# IDD_measurement.net
KiCad netlist of a schematic drawn in Altium Designer
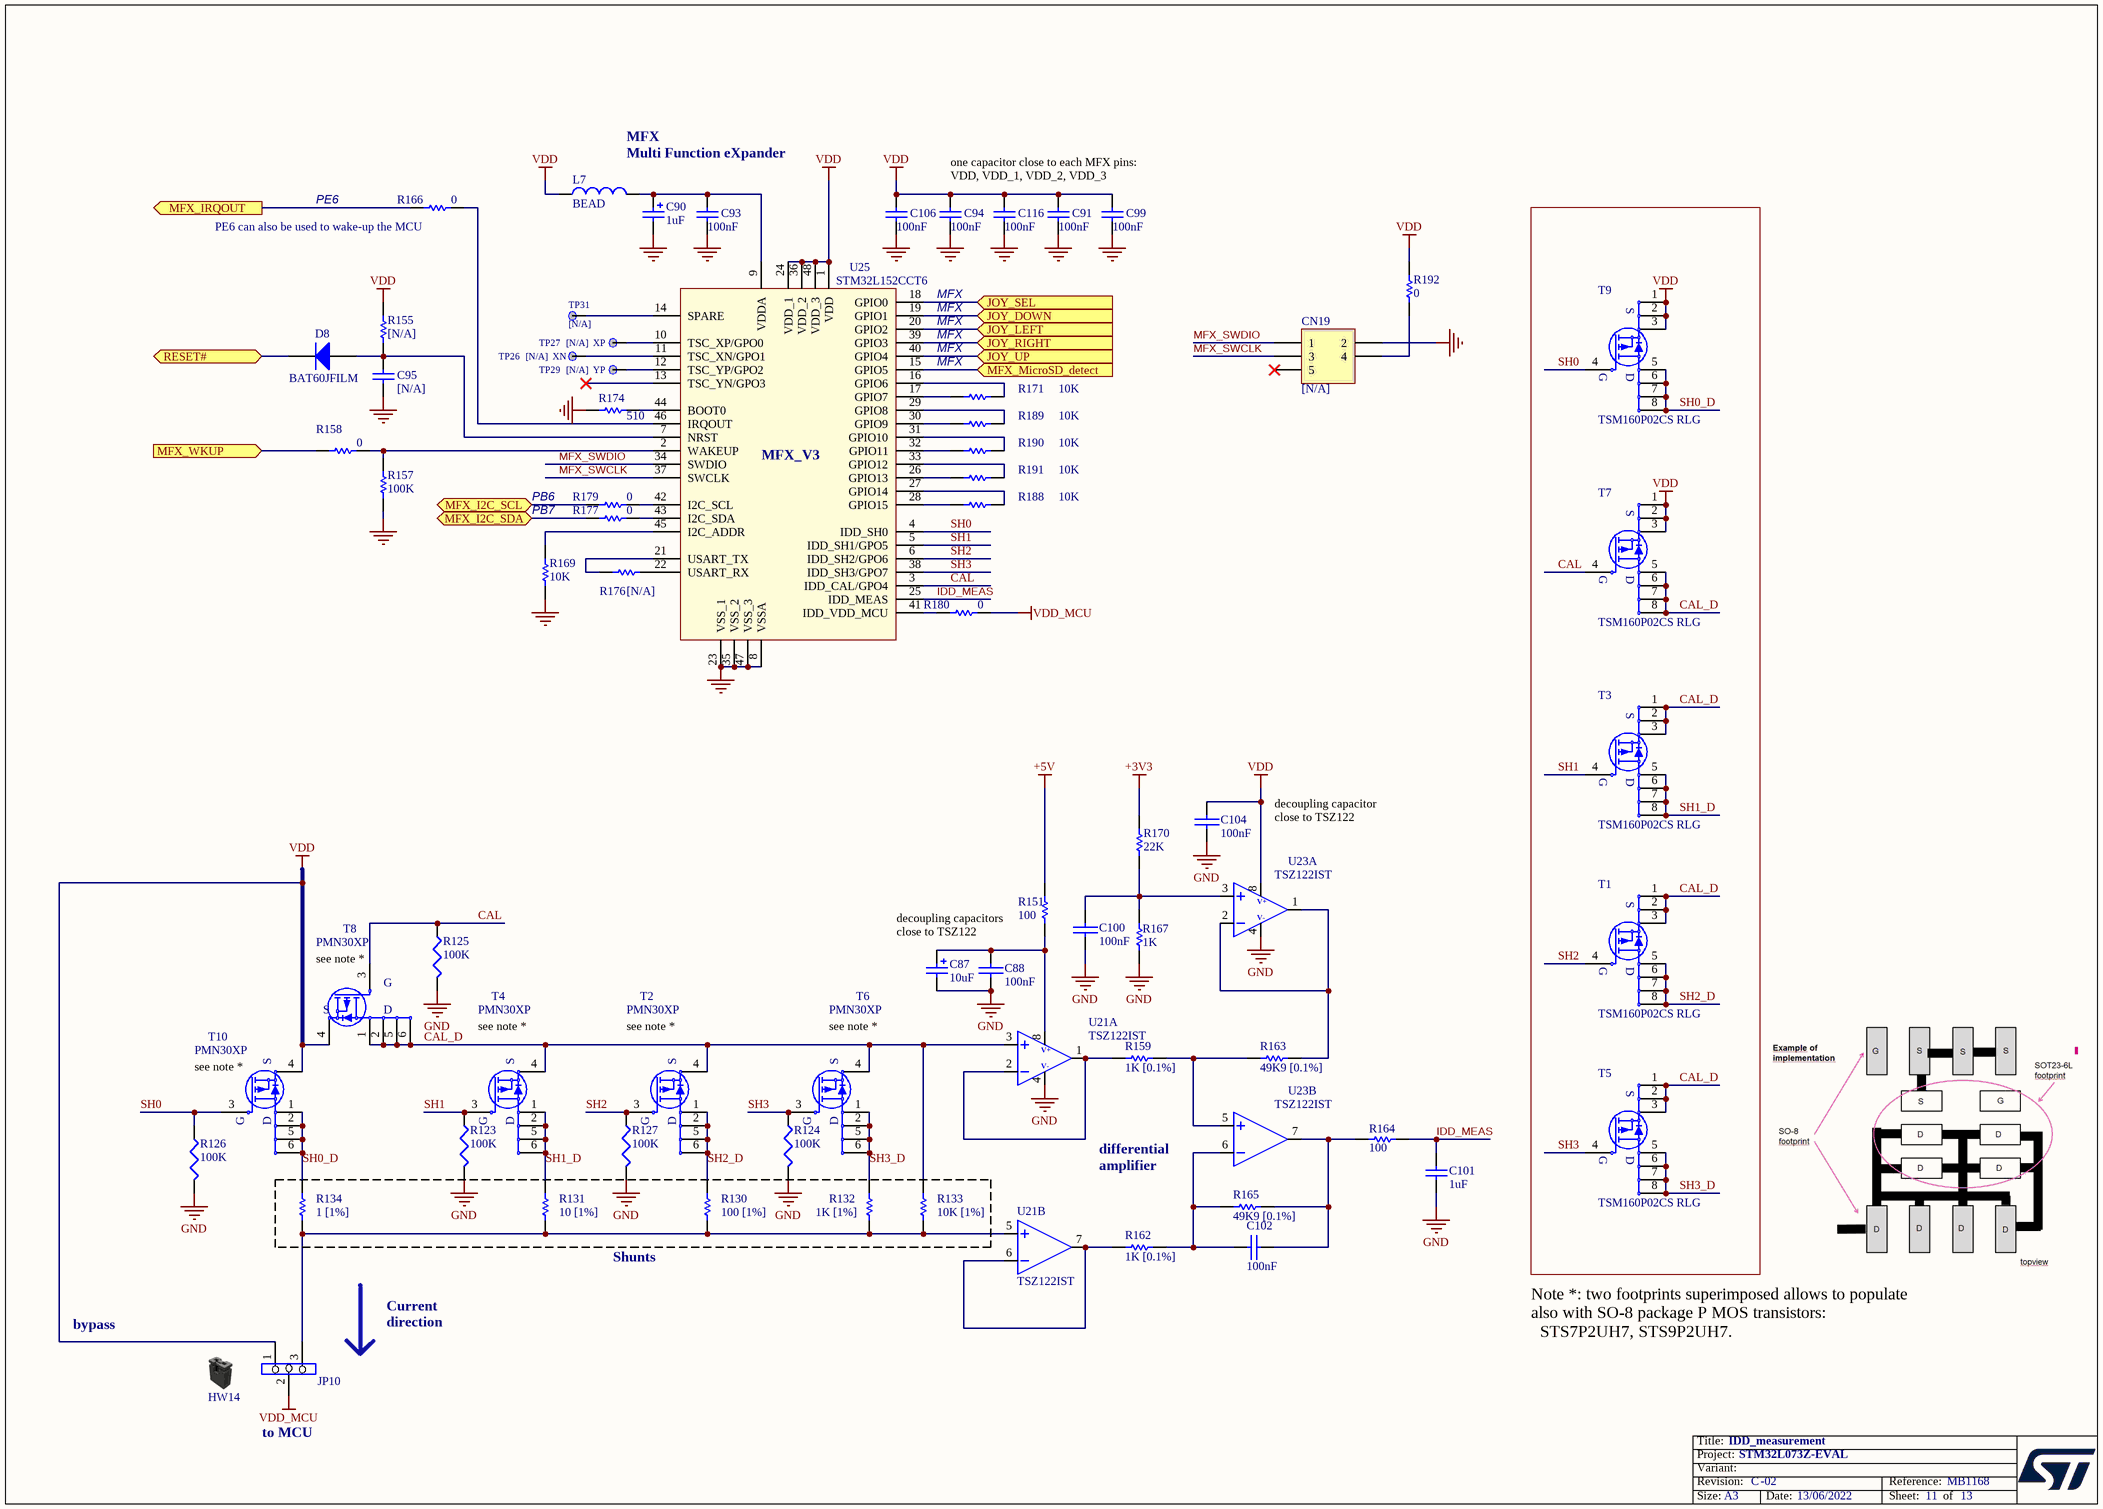
[diagram p0: IDD_measurement.SchDoc]

(export (version "E")
  (design (tool "Eeschema 10.0.6"))
  (components
    (comp (ref "C87")
      (value "10uF")
      (footprint "TAN-A")
      (description "Polarized Capacitor (Radial)")
      (fields (field (name "PUBLISHER") "Altium Limited"))
      (libsource (lib "Miscellaneous Devices") (part "Cap Pol1"))
    )
    (comp (ref "C88") (value "100nF") (footprint "0402C") (libsource (lib "*") (part "CAP")))
    (comp (ref "C90")
      (value "1uF")
      (footprint "TAN-A")
      (description "Polarized Capacitor")
      (libsource (lib "MCD_TOOLS") (part "Cap_1uF_POL_10%_TANA"))
    )
    (comp (ref "C91")
      (value "100nF")
      (footprint "0402C")
      (description "Capacitor,100nF,16V,X7R,10%,0402,YAGEO")
      (libsource (lib "MCD_TOOLS") (part "Cap_100nF_X7R_10%_0402"))
    )
    (comp (ref "C93")
      (value "100nF")
      (footprint "0402C")
      (description "Capacitor,100nF,16V,X7R,10%,0402,YAGEO")
      (libsource (lib "MCD_TOOLS") (part "Cap_100nF_X7R_10%_0402"))
    )
    (comp (ref "C94")
      (value "100nF")
      (footprint "0402C")
      (description "Capacitor,100nF,16V,X7R,10%,0402,YAGEO")
      (libsource (lib "MCD_TOOLS") (part "Cap_100nF_X7R_10%_0402"))
    )
    (comp (ref "C95")
      (value "[N/A]")
      (footprint "0603C")
      (description "Capacitor")
      (fields (field (name "PUBLISHER") "Altium Limited"))
      (libsource (lib "Miscellaneous Devices") (part "cap"))
    )
    (comp (ref "C99")
      (value "100nF")
      (footprint "0402C")
      (description "Capacitor,100nF,16V,X7R,10%,0402,YAGEO")
      (libsource (lib "MCD_TOOLS") (part "Cap_100nF_X7R_10%_0402"))
    )
    (comp (ref "C100") (value "100nF") (footprint "0402C") (libsource (lib "*") (part "CAP")))
    (comp (ref "C101")
      (value "1uF")
      (footprint "0603C")
      (description "Capacitor")
      (fields (field (name "PUBLISHER") "Altium Limited"))
      (libsource (lib "Miscellaneous Devices") (part "CAP"))
    )
    (comp (ref "C102") (value "100nF") (footprint "0402C") (libsource (lib "*") (part "CAP")))
    (comp (ref "C104") (value "100nF") (footprint "0402C") (libsource (lib "*") (part "CAP")))
    (comp (ref "C106")
      (value "100nF")
      (footprint "0402C")
      (description "Capacitor,100nF,16V,X7R,10%,0402,YAGEO")
      (libsource (lib "MCD_TOOLS") (part "Cap_100nF_X7R_10%_0402"))
    )
    (comp (ref "C116")
      (value "100nF")
      (footprint "0402C")
      (description "Capacitor,100nF,16V,X7R,10%,0402,YAGEO")
      (libsource (lib "MCD_TOOLS") (part "Cap_100nF_X7R_10%_0402"))
    )
    (comp (ref "CN19")
      (value "[N/A]")
      (footprint "HDR_2X3-1_2R54-6")
      (description "Header, 3-Pin, Dual row")
      (fields (field (name "PUBLISHER") "Altium Limited"))
      (libsource (lib "Miscellaneous Connectors") (part "Header 3X2"))
    )
    (comp (ref "D8")
      (value "BAT60JFILM")
      (footprint "SOD-323")
      (description "Default Diode")
      (fields (field (name "PUBLISHER") "Altium Limited"))
      (libsource (lib "MB1144_1") (part "Diode"))
    )
    (comp (ref "HW14") (value "Shunt Black 2.54mm") (libsource (lib "MB1168") (part "Shunt Black 2.54mm")))
    (comp (ref "JP10") (value "~") (footprint "SIP3") (libsource (lib "STR910_SCHLIB") (part "Jumper3")))
    (comp (ref "L7")
      (value "BEAD")
      (footprint "0603L")
      (description "Bead,600R,350mA,0603")
      (libsource (lib "MCD_TOOLS") (part "BEAD_600R_350MA_0603"))
    )
    (comp (ref "R123")
      (value "100K")
      (footprint "0402R")
      (description "Resistor")
      (libsource (lib "*") (part "RES1"))
    )
    (comp (ref "R124")
      (value "100K")
      (footprint "0402R")
      (description "Resistor")
      (libsource (lib "*") (part "RES1"))
    )
    (comp (ref "R125")
      (value "100K")
      (footprint "0402R")
      (description "Resistor")
      (libsource (lib "*") (part "RES1"))
    )
    (comp (ref "R126")
      (value "100K")
      (footprint "0402R")
      (description "Resistor")
      (libsource (lib "*") (part "RES1"))
    )
    (comp (ref "R127")
      (value "100K")
      (footprint "0402R")
      (description "Resistor")
      (libsource (lib "*") (part "RES1"))
    )
    (comp (ref "R130")
      (value "100 [1%]")
      (footprint "0603R")
      (description "Resistor")
      (fields (field (name "PUBLISHER") "Altium Limited"))
      (libsource (lib "Miscellaneous Devices") (part "res1"))
    )
    (comp (ref "R131")
      (value "10 [1%]")
      (footprint "0603R")
      (description "Resistor")
      (fields (field (name "PUBLISHER") "Altium Limited"))
      (libsource (lib "Miscellaneous Devices") (part "res1"))
    )
    (comp (ref "R132")
      (value "1K [1%]")
      (footprint "0603R")
      (description "Resistor")
      (fields (field (name "PUBLISHER") "Altium Limited"))
      (libsource (lib "Miscellaneous Devices") (part "res1"))
    )
    (comp (ref "R133")
      (value "10K [1%]")
      (footprint "0603R")
      (description "Resistor")
      (fields (field (name "PUBLISHER") "Altium Limited"))
      (libsource (lib "Miscellaneous Devices") (part "res1"))
    )
    (comp (ref "R134")
      (value "1 [1%]")
      (footprint "0603R")
      (description "Resistor")
      (fields (field (name "PUBLISHER") "Altium Limited"))
      (libsource (lib "Miscellaneous Devices") (part "res1"))
    )
    (comp (ref "R151")
      (value "100")
      (footprint "0402R")
      (description "Resistor")
      (fields (field (name "PUBLISHER") "Altium Limited"))
      (libsource (lib "Miscellaneous Devices") (part "res1"))
    )
    (comp (ref "R155")
      (value "[N/A]")
      (footprint "0603R")
      (description "Resistor")
      (fields (field (name "PUBLISHER") "Altium Limited"))
      (libsource (lib "Miscellaneous Devices") (part "Res1"))
    )
    (comp (ref "R157")
      (value "100K")
      (footprint "0402R")
      (description "Resistor 0402 / 0603 / 0805")
      (libsource (lib "MCD_TOOLS") (part "Resistor_ST"))
    )
    (comp (ref "R158")
      (value "0")
      (footprint "0603R")
      (description "Resistor")
      (fields (field (name "PUBLISHER") "Altium Limited"))
      (libsource (lib "Miscellaneous Devices") (part "Res1"))
    )
    (comp (ref "R159")
      (value "1K [0.1%]")
      (footprint "0603R")
      (description "Resistor")
      (fields (field (name "PUBLISHER") "Altium Limited"))
      (libsource (lib "Miscellaneous Devices") (part "res1"))
    )
    (comp (ref "R162")
      (value "1K [0.1%]")
      (footprint "0603R")
      (description "Resistor")
      (fields (field (name "PUBLISHER") "Altium Limited"))
      (libsource (lib "Miscellaneous Devices") (part "res1"))
    )
    (comp (ref "R163")
      (value "49K9 [0.1%]")
      (footprint "0603R")
      (description "Resistor")
      (fields (field (name "PUBLISHER") "Altium Limited"))
      (libsource (lib "Miscellaneous Devices") (part "res1"))
    )
    (comp (ref "R164")
      (value "100")
      (footprint "0402R")
      (description "Resistor")
      (fields (field (name "PUBLISHER") "Altium Limited"))
      (libsource (lib "Miscellaneous Devices") (part "Res1"))
    )
    (comp (ref "R165")
      (value "49K9 [0.1%]")
      (footprint "0603R")
      (description "Resistor")
      (fields (field (name "PUBLISHER") "Altium Limited"))
      (libsource (lib "Miscellaneous Devices") (part "res1"))
    )
    (comp (ref "R166")
      (value "0")
      (footprint "0603R")
      (description "Resistor")
      (fields (field (name "PUBLISHER") "Altium Limited"))
      (libsource (lib "Miscellaneous Devices") (part "Res1"))
    )
    (comp (ref "R167")
      (value "1K")
      (footprint "0402R")
      (description "Resistor")
      (fields (field (name "PUBLISHER") "Altium Limited"))
      (libsource (lib "Miscellaneous Devices") (part "Res1"))
    )
    (comp (ref "R169")
      (value "10K")
      (footprint "0603R")
      (description "Resistor")
      (fields (field (name "PUBLISHER") "Altium Limited"))
      (libsource (lib "Miscellaneous Devices") (part "res1"))
    )
    (comp (ref "R170")
      (value "22K")
      (footprint "0603R")
      (description "Resistor")
      (fields (field (name "PUBLISHER") "Altium Limited"))
      (libsource (lib "Miscellaneous Devices") (part "res1"))
    )
    (comp (ref "R171")
      (value "10K")
      (footprint "0603R")
      (description "Resistor")
      (fields (field (name "PUBLISHER") "Altium Limited"))
      (libsource (lib "Miscellaneous Devices") (part "res1"))
    )
    (comp (ref "R174")
      (value "510")
      (footprint "0402R")
      (description "Resistor 0402 / 0603 / 0805")
      (libsource (lib "MCD_TOOLS") (part "Resistor_ST"))
    )
    (comp (ref "R176")
      (value "[N/A]")
      (footprint "0603R")
      (description "Resistor")
      (fields (field (name "PUBLISHER") "Altium Limited"))
      (libsource (lib "Miscellaneous Devices") (part "res1"))
    )
    (comp (ref "R177")
      (value "0")
      (footprint "0603R")
      (description "Resistor")
      (fields (field (name "PUBLISHER") "Altium Limited"))
      (libsource (lib "Miscellaneous Devices") (part "Res1"))
    )
    (comp (ref "R179")
      (value "0")
      (footprint "0603R")
      (description "Resistor")
      (fields (field (name "PUBLISHER") "Altium Limited"))
      (libsource (lib "Miscellaneous Devices") (part "Res1"))
    )
    (comp (ref "R180")
      (value "0")
      (footprint "0603R")
      (description "Resistor")
      (fields (field (name "PUBLISHER") "Altium Limited"))
      (libsource (lib "Miscellaneous Devices") (part "Res1"))
    )
    (comp (ref "R188")
      (value "10K")
      (footprint "0603R")
      (description "Resistor")
      (fields (field (name "PUBLISHER") "Altium Limited"))
      (libsource (lib "Miscellaneous Devices") (part "res1"))
    )
    (comp (ref "R189")
      (value "10K")
      (footprint "0603R")
      (description "Resistor")
      (fields (field (name "PUBLISHER") "Altium Limited"))
      (libsource (lib "Miscellaneous Devices") (part "res1"))
    )
    (comp (ref "R190")
      (value "10K")
      (footprint "0603R")
      (description "Resistor")
      (fields (field (name "PUBLISHER") "Altium Limited"))
      (libsource (lib "Miscellaneous Devices") (part "res1"))
    )
    (comp (ref "R191")
      (value "10K")
      (footprint "0603R")
      (description "Resistor")
      (fields (field (name "PUBLISHER") "Altium Limited"))
      (libsource (lib "Miscellaneous Devices") (part "res1"))
    )
    (comp (ref "R192")
      (value "0")
      (footprint "0603R")
      (description "Resistor")
      (fields (field (name "PUBLISHER") "Altium Limited"))
      (libsource (lib "Miscellaneous Devices") (part "Res1"))
    )
    (comp (ref "T1")
      (value "TSM160P02CS RLG")
      (footprint "SOIC8_1R27_4R9X6")
      (description "STripFET VII Power MOSFET, P-CHANNEL 20V - 0.023 - 7A - SO-8")
      (libsource (lib "MCD_TOOLS") (part "STS7P2UH7"))
    )
    (comp (ref "T2")
      (value "PMN30XP")
      (footprint "SOT23-6L")
      (description "STripFET VII DeepGATE Power MOSFET, P-CHANNEL 20 V, 0.0146, 7 A - SOT23-6L")
      (libsource (lib "MCD_TOOLS") (part "STT7P2UH7"))
    )
    (comp (ref "T3")
      (value "TSM160P02CS RLG")
      (footprint "SOIC8_1R27_4R9X6")
      (description "STripFET VII Power MOSFET, P-CHANNEL 20V - 0.023 - 7A - SO-8")
      (libsource (lib "MCD_TOOLS") (part "STS7P2UH7"))
    )
    (comp (ref "T4")
      (value "PMN30XP")
      (footprint "SOT23-6L")
      (description "STripFET VII DeepGATE Power MOSFET, P-CHANNEL 20 V, 0.0146, 7 A - SOT23-6L")
      (libsource (lib "MCD_TOOLS") (part "STT7P2UH7"))
    )
    (comp (ref "T5")
      (value "TSM160P02CS RLG")
      (footprint "SOIC8_1R27_4R9X6")
      (description "STripFET VII Power MOSFET, P-CHANNEL 20V - 0.023 - 7A - SO-8")
      (libsource (lib "MCD_TOOLS") (part "STS7P2UH7"))
    )
    (comp (ref "T6")
      (value "PMN30XP")
      (footprint "SOT23-6L")
      (description "STripFET VII DeepGATE Power MOSFET, P-CHANNEL 20 V, 0.0146, 7 A - SOT23-6L")
      (libsource (lib "MCD_TOOLS") (part "STT7P2UH7"))
    )
    (comp (ref "T7")
      (value "TSM160P02CS RLG")
      (footprint "SOIC8_1R27_4R9X6")
      (description "STripFET VII Power MOSFET, P-CHANNEL 20V - 0.023 - 7A - SO-8")
      (libsource (lib "MCD_TOOLS") (part "STS7P2UH7"))
    )
    (comp (ref "T8")
      (value "PMN30XP")
      (footprint "SOT23-6L")
      (description "STripFET VII DeepGATE Power MOSFET, P-CHANNEL 20 V, 0.0146, 7 A - SOT23-6L")
      (libsource (lib "MCD_TOOLS") (part "STT7P2UH7"))
    )
    (comp (ref "T9")
      (value "TSM160P02CS RLG")
      (footprint "SOIC8_1R27_4R9X6")
      (description "STripFET VII Power MOSFET, P-CHANNEL 20V - 0.023 - 7A - SO-8")
      (libsource (lib "MCD_TOOLS") (part "STS7P2UH7"))
    )
    (comp (ref "T10")
      (value "PMN30XP")
      (footprint "SOT23-6L")
      (description "STripFET VII DeepGATE Power MOSFET, P-CHANNEL 20 V, 0.0146, 7 A - SOT23-6L")
      (libsource (lib "MCD_TOOLS") (part "STT7P2UH7"))
    )
    (comp (ref "TP26")
      (value "[N/A]")
      (footprint "TP")
      (fields (field (name "SILKSCREEN") "XN"))
      (libsource (lib "*") (part "TP"))
    )
    (comp (ref "TP27")
      (value "[N/A]")
      (footprint "TP")
      (fields (field (name "SILKSCREEN") "XP"))
      (libsource (lib "*") (part "TP"))
    )
    (comp (ref "TP29")
      (value "[N/A]")
      (footprint "TP")
      (fields (field (name "SILKSCREEN") "YP"))
      (libsource (lib "*") (part "TP"))
    )
    (comp (ref "TP31") (value "[N/A]") (footprint "TP") (libsource (lib "*") (part "TP")))
    (comp (ref "U21")
      (value "TSZ122IST")
      (footprint "MSOP8_0R65_3X4R9")
      (libsource (lib "Lib_stella") (part "AOP-8PINS"))
    )
    (comp (ref "U23")
      (value "TSZ122IST")
      (footprint "MSOP8_0R65_3X4R9")
      (libsource (lib "Lib_stella") (part "AOP-8PINS"))
    )
    (comp (ref "U25")
      (value "STM32L152CCT6")
      (footprint "LQFP48_0R5_9X9")
      (description "Multifunction expander")
      (libsource (lib "MB1168_1") (part "MFX_V3"))
    )
  )
  (nets
    (net (code "1") (name "+3V3") (class "Default")
      (node (ref "R170") (pin "1") (pinfunction "1_1") (pintype "passive"))
    )
    (net (code "2") (name "+5V") (class "Default")
      (node (ref "R151") (pin "1") (pinfunction "1_1") (pintype "passive"))
    )
    (net (code "3") (name "/CAL") (class "Default")
      (node (ref "R125") (pin "1") (pinfunction "1_1") (pintype "passive"))
      (node (ref "T7") (pin "4") (pinfunction "G_4") (pintype "passive"))
      (node (ref "T8") (pin "3") (pinfunction "G_3") (pintype "passive"))
      (node (ref "U25") (pin "3") (pinfunction "IDD_CAL/GPO4_3") (pintype "passive"))
    )
    (net (code "4") (name "/CAL_D") (class "Default")
      (node (ref "R133") (pin "2") (pinfunction "2_2") (pintype "passive"))
      (node (ref "T1") (pin "1") (pinfunction "S_1") (pintype "passive"))
      (node (ref "T1") (pin "2") (pinfunction "S_2") (pintype "passive"))
      (node (ref "T1") (pin "3") (pinfunction "S_3") (pintype "passive"))
      (node (ref "T2") (pin "4") (pinfunction "S_4") (pintype "passive"))
      (node (ref "T3") (pin "1") (pinfunction "S_1") (pintype "passive"))
      (node (ref "T3") (pin "2") (pinfunction "S_2") (pintype "passive"))
      (node (ref "T3") (pin "3") (pinfunction "S_3") (pintype "passive"))
      (node (ref "T4") (pin "4") (pinfunction "S_4") (pintype "passive"))
      (node (ref "T5") (pin "1") (pinfunction "S_1") (pintype "passive"))
      (node (ref "T5") (pin "2") (pinfunction "S_2") (pintype "passive"))
      (node (ref "T5") (pin "3") (pinfunction "S_3") (pintype "passive"))
      (node (ref "T6") (pin "4") (pinfunction "S_4") (pintype "passive"))
      (node (ref "T7") (pin "5") (pinfunction "D_5") (pintype "passive"))
      (node (ref "T7") (pin "6") (pinfunction "D_6") (pintype "passive"))
      (node (ref "T7") (pin "7") (pinfunction "D_7") (pintype "passive"))
      (node (ref "T7") (pin "8") (pinfunction "D_8") (pintype "passive"))
      (node (ref "T8") (pin "1") (pinfunction "S_1") (pintype "passive"))
      (node (ref "T8") (pin "2") (pinfunction "S_2") (pintype "passive"))
      (node (ref "T8") (pin "5") (pinfunction "D_5") (pintype "passive"))
      (node (ref "T8") (pin "6") (pinfunction "D_6") (pintype "passive"))
      (node (ref "U21") (pin "3") (pintype "passive"))
    )
    (net (code "5") (name "/IDD_MEAS") (class "Default")
      (node (ref "C101") (pin "2") (pinfunction "2_2") (pintype "passive"))
      (node (ref "R164") (pin "1") (pinfunction "1_1") (pintype "passive"))
      (node (ref "U25") (pin "25") (pinfunction "IDD_MEAS_25") (pintype "passive"))
    )
    (net (code "6") (name "/JOY_DOWN") (class "Default")
      (node (ref "U25") (pin "19") (pinfunction "GPIO1_19") (pintype "passive"))
    )
    (net (code "7") (name "/JOY_LEFT") (class "Default")
      (node (ref "U25") (pin "20") (pinfunction "GPIO2_20") (pintype "passive"))
    )
    (net (code "8") (name "/JOY_RIGHT") (class "Default")
      (node (ref "U25") (pin "39") (pinfunction "GPIO3_39") (pintype "passive"))
    )
    (net (code "9") (name "/JOY_SEL") (class "Default")
      (node (ref "U25") (pin "18") (pinfunction "GPIO0_18") (pintype "passive"))
    )
    (net (code "10") (name "/JOY_UP") (class "Default")
      (node (ref "U25") (pin "40") (pinfunction "GPIO4_40") (pintype "passive"))
    )
    (net (code "11") (name "/MFX_I2C_SCL") (class "Default")
      (node (ref "R179") (pin "1") (pinfunction "1_1") (pintype "passive"))
    )
    (net (code "12") (name "/MFX_I2C_SDA") (class "Default")
      (node (ref "R177") (pin "1") (pinfunction "1_1") (pintype "passive"))
    )
    (net (code "13") (name "/MFX_IRQOUT") (class "Default")
      (node (ref "R166") (pin "1") (pinfunction "1_1") (pintype "passive"))
    )
    (net (code "14") (name "/MFX_MicroSD_detect") (class "Default")
      (node (ref "U25") (pin "15") (pinfunction "GPIO5_15") (pintype "passive"))
    )
    (net (code "15") (name "/MFX_SWCLK") (class "Default")
      (node (ref "CN19") (pin "3") (pinfunction "3_3") (pintype "passive"))
      (node (ref "U25") (pin "37") (pinfunction "SWCLK_37") (pintype "passive"))
    )
    (net (code "16") (name "/MFX_SWDIO") (class "Default")
      (node (ref "CN19") (pin "1") (pinfunction "1_1") (pintype "passive"))
      (node (ref "U25") (pin "34") (pinfunction "SWDIO_34") (pintype "passive"))
    )
    (net (code "17") (name "/MFX_WKUP") (class "Default")
      (node (ref "R158") (pin "1") (pinfunction "1_1") (pintype "passive"))
    )
    (net (code "18") (name "/RESET#") (class "Default")
      (node (ref "D8") (pin "2") (pinfunction "K_2") (pintype "passive"))
    )
    (net (code "19") (name "/SH0") (class "Default")
      (node (ref "R126") (pin "1") (pinfunction "1_1") (pintype "passive"))
      (node (ref "T10") (pin "3") (pinfunction "G_3") (pintype "passive"))
      (node (ref "T9") (pin "4") (pinfunction "G_4") (pintype "passive"))
      (node (ref "U25") (pin "4") (pinfunction "IDD_SH0_4") (pintype "passive"))
    )
    (net (code "20") (name "/SH0_D") (class "Default")
      (node (ref "R134") (pin "2") (pinfunction "2_2") (pintype "passive"))
      (node (ref "T10") (pin "1") (pinfunction "S_1") (pintype "passive"))
      (node (ref "T10") (pin "2") (pinfunction "S_2") (pintype "passive"))
      (node (ref "T10") (pin "5") (pinfunction "D_5") (pintype "passive"))
      (node (ref "T10") (pin "6") (pinfunction "D_6") (pintype "passive"))
      (node (ref "T9") (pin "5") (pinfunction "D_5") (pintype "passive"))
      (node (ref "T9") (pin "6") (pinfunction "D_6") (pintype "passive"))
      (node (ref "T9") (pin "7") (pinfunction "D_7") (pintype "passive"))
      (node (ref "T9") (pin "8") (pinfunction "D_8") (pintype "passive"))
    )
    (net (code "21") (name "/SH1") (class "Default")
      (node (ref "R123") (pin "1") (pinfunction "1_1") (pintype "passive"))
      (node (ref "T3") (pin "4") (pinfunction "G_4") (pintype "passive"))
      (node (ref "T4") (pin "3") (pinfunction "G_3") (pintype "passive"))
      (node (ref "U25") (pin "5") (pinfunction "IDD_SH1/GPO5_5") (pintype "passive"))
    )
    (net (code "22") (name "/SH1_D") (class "Default")
      (node (ref "R131") (pin "2") (pinfunction "2_2") (pintype "passive"))
      (node (ref "T3") (pin "5") (pinfunction "D_5") (pintype "passive"))
      (node (ref "T3") (pin "6") (pinfunction "D_6") (pintype "passive"))
      (node (ref "T3") (pin "7") (pinfunction "D_7") (pintype "passive"))
      (node (ref "T3") (pin "8") (pinfunction "D_8") (pintype "passive"))
      (node (ref "T4") (pin "1") (pinfunction "S_1") (pintype "passive"))
      (node (ref "T4") (pin "2") (pinfunction "S_2") (pintype "passive"))
      (node (ref "T4") (pin "5") (pinfunction "D_5") (pintype "passive"))
      (node (ref "T4") (pin "6") (pinfunction "D_6") (pintype "passive"))
    )
    (net (code "23") (name "/SH2") (class "Default")
      (node (ref "R127") (pin "1") (pinfunction "1_1") (pintype "passive"))
      (node (ref "T1") (pin "4") (pinfunction "G_4") (pintype "passive"))
      (node (ref "T2") (pin "3") (pinfunction "G_3") (pintype "passive"))
      (node (ref "U25") (pin "6") (pinfunction "IDD_SH2/GPO6_6") (pintype "passive"))
    )
    (net (code "24") (name "/SH2_D") (class "Default")
      (node (ref "R130") (pin "2") (pinfunction "2_2") (pintype "passive"))
      (node (ref "T1") (pin "5") (pinfunction "D_5") (pintype "passive"))
      (node (ref "T1") (pin "6") (pinfunction "D_6") (pintype "passive"))
      (node (ref "T1") (pin "7") (pinfunction "D_7") (pintype "passive"))
      (node (ref "T1") (pin "8") (pinfunction "D_8") (pintype "passive"))
      (node (ref "T2") (pin "1") (pinfunction "S_1") (pintype "passive"))
      (node (ref "T2") (pin "2") (pinfunction "S_2") (pintype "passive"))
      (node (ref "T2") (pin "5") (pinfunction "D_5") (pintype "passive"))
      (node (ref "T2") (pin "6") (pinfunction "D_6") (pintype "passive"))
    )
    (net (code "25") (name "/SH3") (class "Default")
      (node (ref "R124") (pin "1") (pinfunction "1_1") (pintype "passive"))
      (node (ref "T5") (pin "4") (pinfunction "G_4") (pintype "passive"))
      (node (ref "T6") (pin "3") (pinfunction "G_3") (pintype "passive"))
      (node (ref "U25") (pin "38") (pinfunction "IDD_SH3/GPO7_38") (pintype "passive"))
    )
    (net (code "26") (name "/SH3_D") (class "Default")
      (node (ref "R132") (pin "2") (pinfunction "2_2") (pintype "passive"))
      (node (ref "T5") (pin "5") (pinfunction "D_5") (pintype "passive"))
      (node (ref "T5") (pin "6") (pinfunction "D_6") (pintype "passive"))
      (node (ref "T5") (pin "7") (pinfunction "D_7") (pintype "passive"))
      (node (ref "T5") (pin "8") (pinfunction "D_8") (pintype "passive"))
      (node (ref "T6") (pin "1") (pinfunction "S_1") (pintype "passive"))
      (node (ref "T6") (pin "2") (pinfunction "S_2") (pintype "passive"))
      (node (ref "T6") (pin "5") (pinfunction "D_5") (pintype "passive"))
      (node (ref "T6") (pin "6") (pinfunction "D_6") (pintype "passive"))
    )
    (net (code "27") (name "GND") (class "Default")
      (node (ref "C100") (pin "2") (pinfunction "2_2") (pintype "passive"))
      (node (ref "C101") (pin "1") (pinfunction "1_1") (pintype "passive"))
      (node (ref "C104") (pin "2") (pinfunction "2_2") (pintype "passive"))
      (node (ref "C106") (pin "1") (pinfunction "1_1") (pintype "passive"))
      (node (ref "C116") (pin "2") (pinfunction "2_2") (pintype "passive"))
      (node (ref "C87") (pin "2") (pinfunction "2_2") (pintype "passive"))
      (node (ref "C88") (pin "2") (pinfunction "2_2") (pintype "passive"))
      (node (ref "C90") (pin "2") (pinfunction "2_2") (pintype "passive"))
      (node (ref "C91") (pin "1") (pinfunction "1_1") (pintype "passive"))
      (node (ref "C93") (pin "1") (pinfunction "1_1") (pintype "passive"))
      (node (ref "C94") (pin "1") (pinfunction "1_1") (pintype "passive"))
      (node (ref "C95") (pin "1") (pinfunction "1_1") (pintype "passive"))
      (node (ref "C99") (pin "1") (pinfunction "1_1") (pintype "passive"))
      (node (ref "CN19") (pin "2") (pinfunction "2_2") (pintype "passive"))
      (node (ref "R123") (pin "2") (pinfunction "2_2") (pintype "passive"))
      (node (ref "R124") (pin "2") (pinfunction "2_2") (pintype "passive"))
      (node (ref "R125") (pin "2") (pinfunction "2_2") (pintype "passive"))
      (node (ref "R126") (pin "2") (pinfunction "2_2") (pintype "passive"))
      (node (ref "R127") (pin "2") (pinfunction "2_2") (pintype "passive"))
      (node (ref "R157") (pin "2") (pinfunction "2_2") (pintype "passive"))
      (node (ref "R167") (pin "2") (pinfunction "2_2") (pintype "passive"))
      (node (ref "R169") (pin "1") (pinfunction "1_1") (pintype "passive"))
      (node (ref "R174") (pin "2") (pinfunction "2_2") (pintype "passive"))
      (node (ref "U21") (pin "4") (pintype "passive"))
      (node (ref "U23") (pin "4") (pintype "passive"))
      (node (ref "U25") (pin "23") (pinfunction "VSS_1_23") (pintype "passive"))
      (node (ref "U25") (pin "35") (pinfunction "VSS_2_35") (pintype "passive"))
      (node (ref "U25") (pin "47") (pinfunction "VSS_3_47") (pintype "passive"))
      (node (ref "U25") (pin "8") (pinfunction "VSSA_8") (pintype "passive"))
    )
    (net (code "28") (name "Net-(C87-Pad1)") (class "Default")
      (node (ref "C87") (pin "1") (pinfunction "1_1") (pintype "passive"))
      (node (ref "C88") (pin "1") (pinfunction "1_1") (pintype "passive"))
      (node (ref "R151") (pin "2") (pinfunction "2_2") (pintype "passive"))
      (node (ref "U21") (pin "8") (pintype "passive"))
    )
    (net (code "29") (name "Net-(C100-Pad1)") (class "Default")
      (node (ref "C100") (pin "1") (pinfunction "1_1") (pintype "passive"))
      (node (ref "R167") (pin "1") (pinfunction "1_1") (pintype "passive"))
      (node (ref "R170") (pin "2") (pinfunction "2_2") (pintype "passive"))
      (node (ref "U23") (pin "3") (pintype "passive"))
    )
    (net (code "30") (name "Net-(C102-Pad1)") (class "Default")
      (node (ref "C102") (pin "1") (pinfunction "1_1") (pintype "passive"))
      (node (ref "R162") (pin "2") (pinfunction "2_2") (pintype "passive"))
      (node (ref "R165") (pin "1") (pinfunction "1_1") (pintype "passive"))
      (node (ref "U23") (pin "6") (pintype "passive"))
    )
    (net (code "31") (name "Net-(C102-Pad2)") (class "Default")
      (node (ref "C102") (pin "2") (pinfunction "2_2") (pintype "passive"))
      (node (ref "R164") (pin "2") (pinfunction "2_2") (pintype "passive"))
      (node (ref "R165") (pin "2") (pinfunction "2_2") (pintype "passive"))
      (node (ref "U23") (pin "7") (pintype "passive"))
    )
    (net (code "32") (name "Net-(CN19-Pad4)") (class "Default")
      (node (ref "CN19") (pin "4") (pinfunction "4_4") (pintype "passive"))
      (node (ref "R192") (pin "1") (pinfunction "1_1") (pintype "passive"))
    )
    (net (code "33") (name "Net-(D8-A)") (class "Default")
      (node (ref "C95") (pin "2") (pinfunction "2_2") (pintype "passive"))
      (node (ref "D8") (pin "1") (pinfunction "A_1") (pintype "passive"))
      (node (ref "R155") (pin "2") (pinfunction "2_2") (pintype "passive"))
      (node (ref "U25") (pin "7") (pinfunction "NRST_7") (pintype "passive"))
    )
    (net (code "34") (name "Net-(JP10-Pad3)") (class "Default")
      (node (ref "JP10") (pin "3") (pintype "passive"))
      (node (ref "R130") (pin "1") (pinfunction "1_1") (pintype "passive"))
      (node (ref "R131") (pin "1") (pinfunction "1_1") (pintype "passive"))
      (node (ref "R132") (pin "1") (pinfunction "1_1") (pintype "passive"))
      (node (ref "R133") (pin "1") (pinfunction "1_1") (pintype "passive"))
      (node (ref "R134") (pin "1") (pinfunction "1_1") (pintype "passive"))
      (node (ref "U21") (pin "5") (pintype "passive"))
    )
    (net (code "35") (name "Net-(R159-Pad1)") (class "Default")
      (node (ref "R159") (pin "1") (pinfunction "1_1") (pintype "passive"))
      (node (ref "U21") (pin "1") (pintype "passive"))
      (node (ref "U21") (pin "2") (pintype "passive"))
    )
    (net (code "36") (name "Net-(R159-Pad2)") (class "Default")
      (node (ref "R159") (pin "2") (pinfunction "2_2") (pintype "passive"))
      (node (ref "R163") (pin "1") (pinfunction "1_1") (pintype "passive"))
      (node (ref "U23") (pin "5") (pintype "passive"))
    )
    (net (code "37") (name "Net-(R162-Pad1)") (class "Default")
      (node (ref "R162") (pin "1") (pinfunction "1_1") (pintype "passive"))
      (node (ref "U21") (pin "6") (pintype "passive"))
      (node (ref "U21") (pin "7") (pintype "passive"))
    )
    (net (code "38") (name "Net-(R163-Pad2)") (class "Default")
      (node (ref "R163") (pin "2") (pinfunction "2_2") (pintype "passive"))
      (node (ref "U23") (pin "1") (pintype "passive"))
      (node (ref "U23") (pin "2") (pintype "passive"))
    )
    (net (code "39") (name "Net-(U25-BOOT0)") (class "Default")
      (node (ref "R174") (pin "1") (pinfunction "1_1") (pintype "passive"))
      (node (ref "U25") (pin "44") (pinfunction "BOOT0_44") (pintype "passive"))
    )
    (net (code "40") (name "Net-(U25-GPIO6)") (class "Default")
      (node (ref "R171") (pin "2") (pinfunction "2_2") (pintype "passive"))
      (node (ref "U25") (pin "16") (pinfunction "GPIO6_16") (pintype "passive"))
    )
    (net (code "41") (name "Net-(U25-GPIO7)") (class "Default")
      (node (ref "R171") (pin "1") (pinfunction "1_1") (pintype "passive"))
      (node (ref "U25") (pin "17") (pinfunction "GPIO7_17") (pintype "passive"))
    )
    (net (code "42") (name "Net-(U25-GPIO8)") (class "Default")
      (node (ref "R189") (pin "2") (pinfunction "2_2") (pintype "passive"))
      (node (ref "U25") (pin "29") (pinfunction "GPIO8_29") (pintype "passive"))
    )
    (net (code "43") (name "Net-(U25-GPIO9)") (class "Default")
      (node (ref "R189") (pin "1") (pinfunction "1_1") (pintype "passive"))
      (node (ref "U25") (pin "30") (pinfunction "GPIO9_30") (pintype "passive"))
    )
    (net (code "44") (name "Net-(U25-GPIO10)") (class "Default")
      (node (ref "R190") (pin "2") (pinfunction "2_2") (pintype "passive"))
      (node (ref "U25") (pin "31") (pinfunction "GPIO10_31") (pintype "passive"))
    )
    (net (code "45") (name "Net-(U25-GPIO11)") (class "Default")
      (node (ref "R190") (pin "1") (pinfunction "1_1") (pintype "passive"))
      (node (ref "U25") (pin "32") (pinfunction "GPIO11_32") (pintype "passive"))
    )
    (net (code "46") (name "Net-(U25-GPIO12)") (class "Default")
      (node (ref "R191") (pin "2") (pinfunction "2_2") (pintype "passive"))
      (node (ref "U25") (pin "33") (pinfunction "GPIO12_33") (pintype "passive"))
    )
    (net (code "47") (name "Net-(U25-GPIO13)") (class "Default")
      (node (ref "R191") (pin "1") (pinfunction "1_1") (pintype "passive"))
      (node (ref "U25") (pin "26") (pinfunction "GPIO13_26") (pintype "passive"))
    )
    (net (code "48") (name "Net-(U25-GPIO14)") (class "Default")
      (node (ref "R188") (pin "2") (pinfunction "2_2") (pintype "passive"))
      (node (ref "U25") (pin "27") (pinfunction "GPIO14_27") (pintype "passive"))
    )
    (net (code "49") (name "Net-(U25-GPIO15)") (class "Default")
      (node (ref "R188") (pin "1") (pinfunction "1_1") (pintype "passive"))
      (node (ref "U25") (pin "28") (pinfunction "GPIO15_28") (pintype "passive"))
    )
    (net (code "50") (name "Net-(U25-I2C_ADDR)") (class "Default")
      (node (ref "R169") (pin "2") (pinfunction "2_2") (pintype "passive"))
      (node (ref "U25") (pin "45") (pinfunction "I2C_ADDR_45") (pintype "passive"))
    )
    (net (code "51") (name "Net-(U25-I2C_SCL)") (class "Default")
      (node (ref "R179") (pin "2") (pinfunction "2_2") (pintype "passive"))
      (node (ref "U25") (pin "42") (pinfunction "I2C_SCL_42") (pintype "passive"))
    )
    (net (code "52") (name "Net-(U25-I2C_SDA)") (class "Default")
      (node (ref "R177") (pin "2") (pinfunction "2_2") (pintype "passive"))
      (node (ref "U25") (pin "43") (pinfunction "I2C_SDA_43") (pintype "passive"))
    )
    (net (code "53") (name "Net-(U25-IDD_VDD_MCU)") (class "Default")
      (node (ref "R180") (pin "1") (pinfunction "1_1") (pintype "passive"))
      (node (ref "U25") (pin "41") (pinfunction "IDD_VDD_MCU_41") (pintype "passive"))
    )
    (net (code "54") (name "Net-(U25-IRQOUT)") (class "Default")
      (node (ref "R166") (pin "2") (pinfunction "2_2") (pintype "passive"))
      (node (ref "U25") (pin "46") (pinfunction "IRQOUT_46") (pintype "passive"))
    )
    (net (code "55") (name "Net-(U25-SPARE)") (class "Default")
      (node (ref "TP31") (pin "1") (pinfunction "1_1") (pintype "passive"))
      (node (ref "U25") (pin "14") (pinfunction "SPARE_14") (pintype "passive"))
    )
    (net (code "56") (name "Net-(U25-TSC_XN{slash}GPO1)") (class "Default")
      (node (ref "TP26") (pin "1") (pinfunction "1_1") (pintype "passive"))
      (node (ref "U25") (pin "11") (pinfunction "TSC_XN/GPO1_11") (pintype "passive"))
    )
    (net (code "57") (name "Net-(U25-TSC_XP{slash}GPO0)") (class "Default")
      (node (ref "TP27") (pin "1") (pinfunction "1_1") (pintype "passive"))
      (node (ref "U25") (pin "10") (pinfunction "TSC_XP/GPO0_10") (pintype "passive"))
    )
    (net (code "58") (name "Net-(U25-TSC_YP{slash}GPO2)") (class "Default")
      (node (ref "TP29") (pin "1") (pinfunction "1_1") (pintype "passive"))
      (node (ref "U25") (pin "12") (pinfunction "TSC_YP/GPO2_12") (pintype "passive"))
    )
    (net (code "59") (name "Net-(U25-USART_RX)") (class "Default")
      (node (ref "R176") (pin "2") (pinfunction "2_2") (pintype "passive"))
      (node (ref "U25") (pin "22") (pinfunction "USART_RX_22") (pintype "passive"))
    )
    (net (code "60") (name "Net-(U25-USART_TX)") (class "Default")
      (node (ref "R176") (pin "1") (pinfunction "1_1") (pintype "passive"))
      (node (ref "U25") (pin "21") (pinfunction "USART_TX_21") (pintype "passive"))
    )
    (net (code "61") (name "Net-(U25-VDDA)") (class "Default")
      (node (ref "C90") (pin "1") (pinfunction "1_1") (pintype "passive"))
      (node (ref "C93") (pin "2") (pinfunction "2_2") (pintype "passive"))
      (node (ref "L7") (pin "2") (pinfunction "2_2") (pintype "passive"))
      (node (ref "U25") (pin "9") (pinfunction "VDDA_9") (pintype "passive"))
    )
    (net (code "62") (name "Net-(U25-WAKEUP)") (class "Default")
      (node (ref "R157") (pin "1") (pinfunction "1_1") (pintype "passive"))
      (node (ref "R158") (pin "2") (pinfunction "2_2") (pintype "passive"))
      (node (ref "U25") (pin "2") (pinfunction "WAKEUP_2") (pintype "passive"))
    )
    (net (code "63") (name "VDD") (class "Default")
      (node (ref "C104") (pin "1") (pinfunction "1_1") (pintype "passive"))
      (node (ref "C106") (pin "2") (pinfunction "2_2") (pintype "passive"))
      (node (ref "C116") (pin "1") (pinfunction "1_1") (pintype "passive"))
      (node (ref "C91") (pin "2") (pinfunction "2_2") (pintype "passive"))
      (node (ref "C94") (pin "2") (pinfunction "2_2") (pintype "passive"))
      (node (ref "C99") (pin "2") (pinfunction "2_2") (pintype "passive"))
      (node (ref "JP10") (pin "1") (pintype "passive"))
      (node (ref "L7") (pin "1") (pinfunction "1_1") (pintype "passive"))
      (node (ref "R155") (pin "1") (pinfunction "1_1") (pintype "passive"))
      (node (ref "R192") (pin "2") (pinfunction "2_2") (pintype "passive"))
      (node (ref "T10") (pin "4") (pinfunction "S_4") (pintype "passive"))
      (node (ref "T7") (pin "1") (pinfunction "S_1") (pintype "passive"))
      (node (ref "T7") (pin "2") (pinfunction "S_2") (pintype "passive"))
      (node (ref "T7") (pin "3") (pinfunction "S_3") (pintype "passive"))
      (node (ref "T8") (pin "4") (pinfunction "S_4") (pintype "passive"))
      (node (ref "T9") (pin "1") (pinfunction "S_1") (pintype "passive"))
      (node (ref "T9") (pin "2") (pinfunction "S_2") (pintype "passive"))
      (node (ref "T9") (pin "3") (pinfunction "S_3") (pintype "passive"))
      (node (ref "U23") (pin "8") (pintype "passive"))
      (node (ref "U25") (pin "1") (pinfunction "VDD_1") (pintype "passive"))
      (node (ref "U25") (pin "24") (pinfunction "VDD_1_24") (pintype "passive"))
      (node (ref "U25") (pin "36") (pinfunction "VDD_2_36") (pintype "passive"))
      (node (ref "U25") (pin "48") (pinfunction "VDD_3_48") (pintype "passive"))
    )
    (net (code "64") (name "VDD_MCU") (class "Default")
      (node (ref "JP10") (pin "2") (pintype "passive"))
      (node (ref "R180") (pin "2") (pinfunction "2_2") (pintype "passive"))
    )
    (net (code "65") (name "unconnected-(CN19-Pad5)") (class "Default")
      (node (ref "CN19") (pin "5") (pinfunction "5_5") (pintype "passive+no_connect"))
    )
    (net (code "66") (name "unconnected-(U25-TSC_YN{slash}GPO3-Pad13)") (class "Default")
      (node (ref "U25") (pin "13") (pinfunction "TSC_YN/GPO3_13") (pintype "passive+no_connect"))
    )
  )
)
